# MCU.net
KiCad netlist of a schematic drawn in Altium Designer
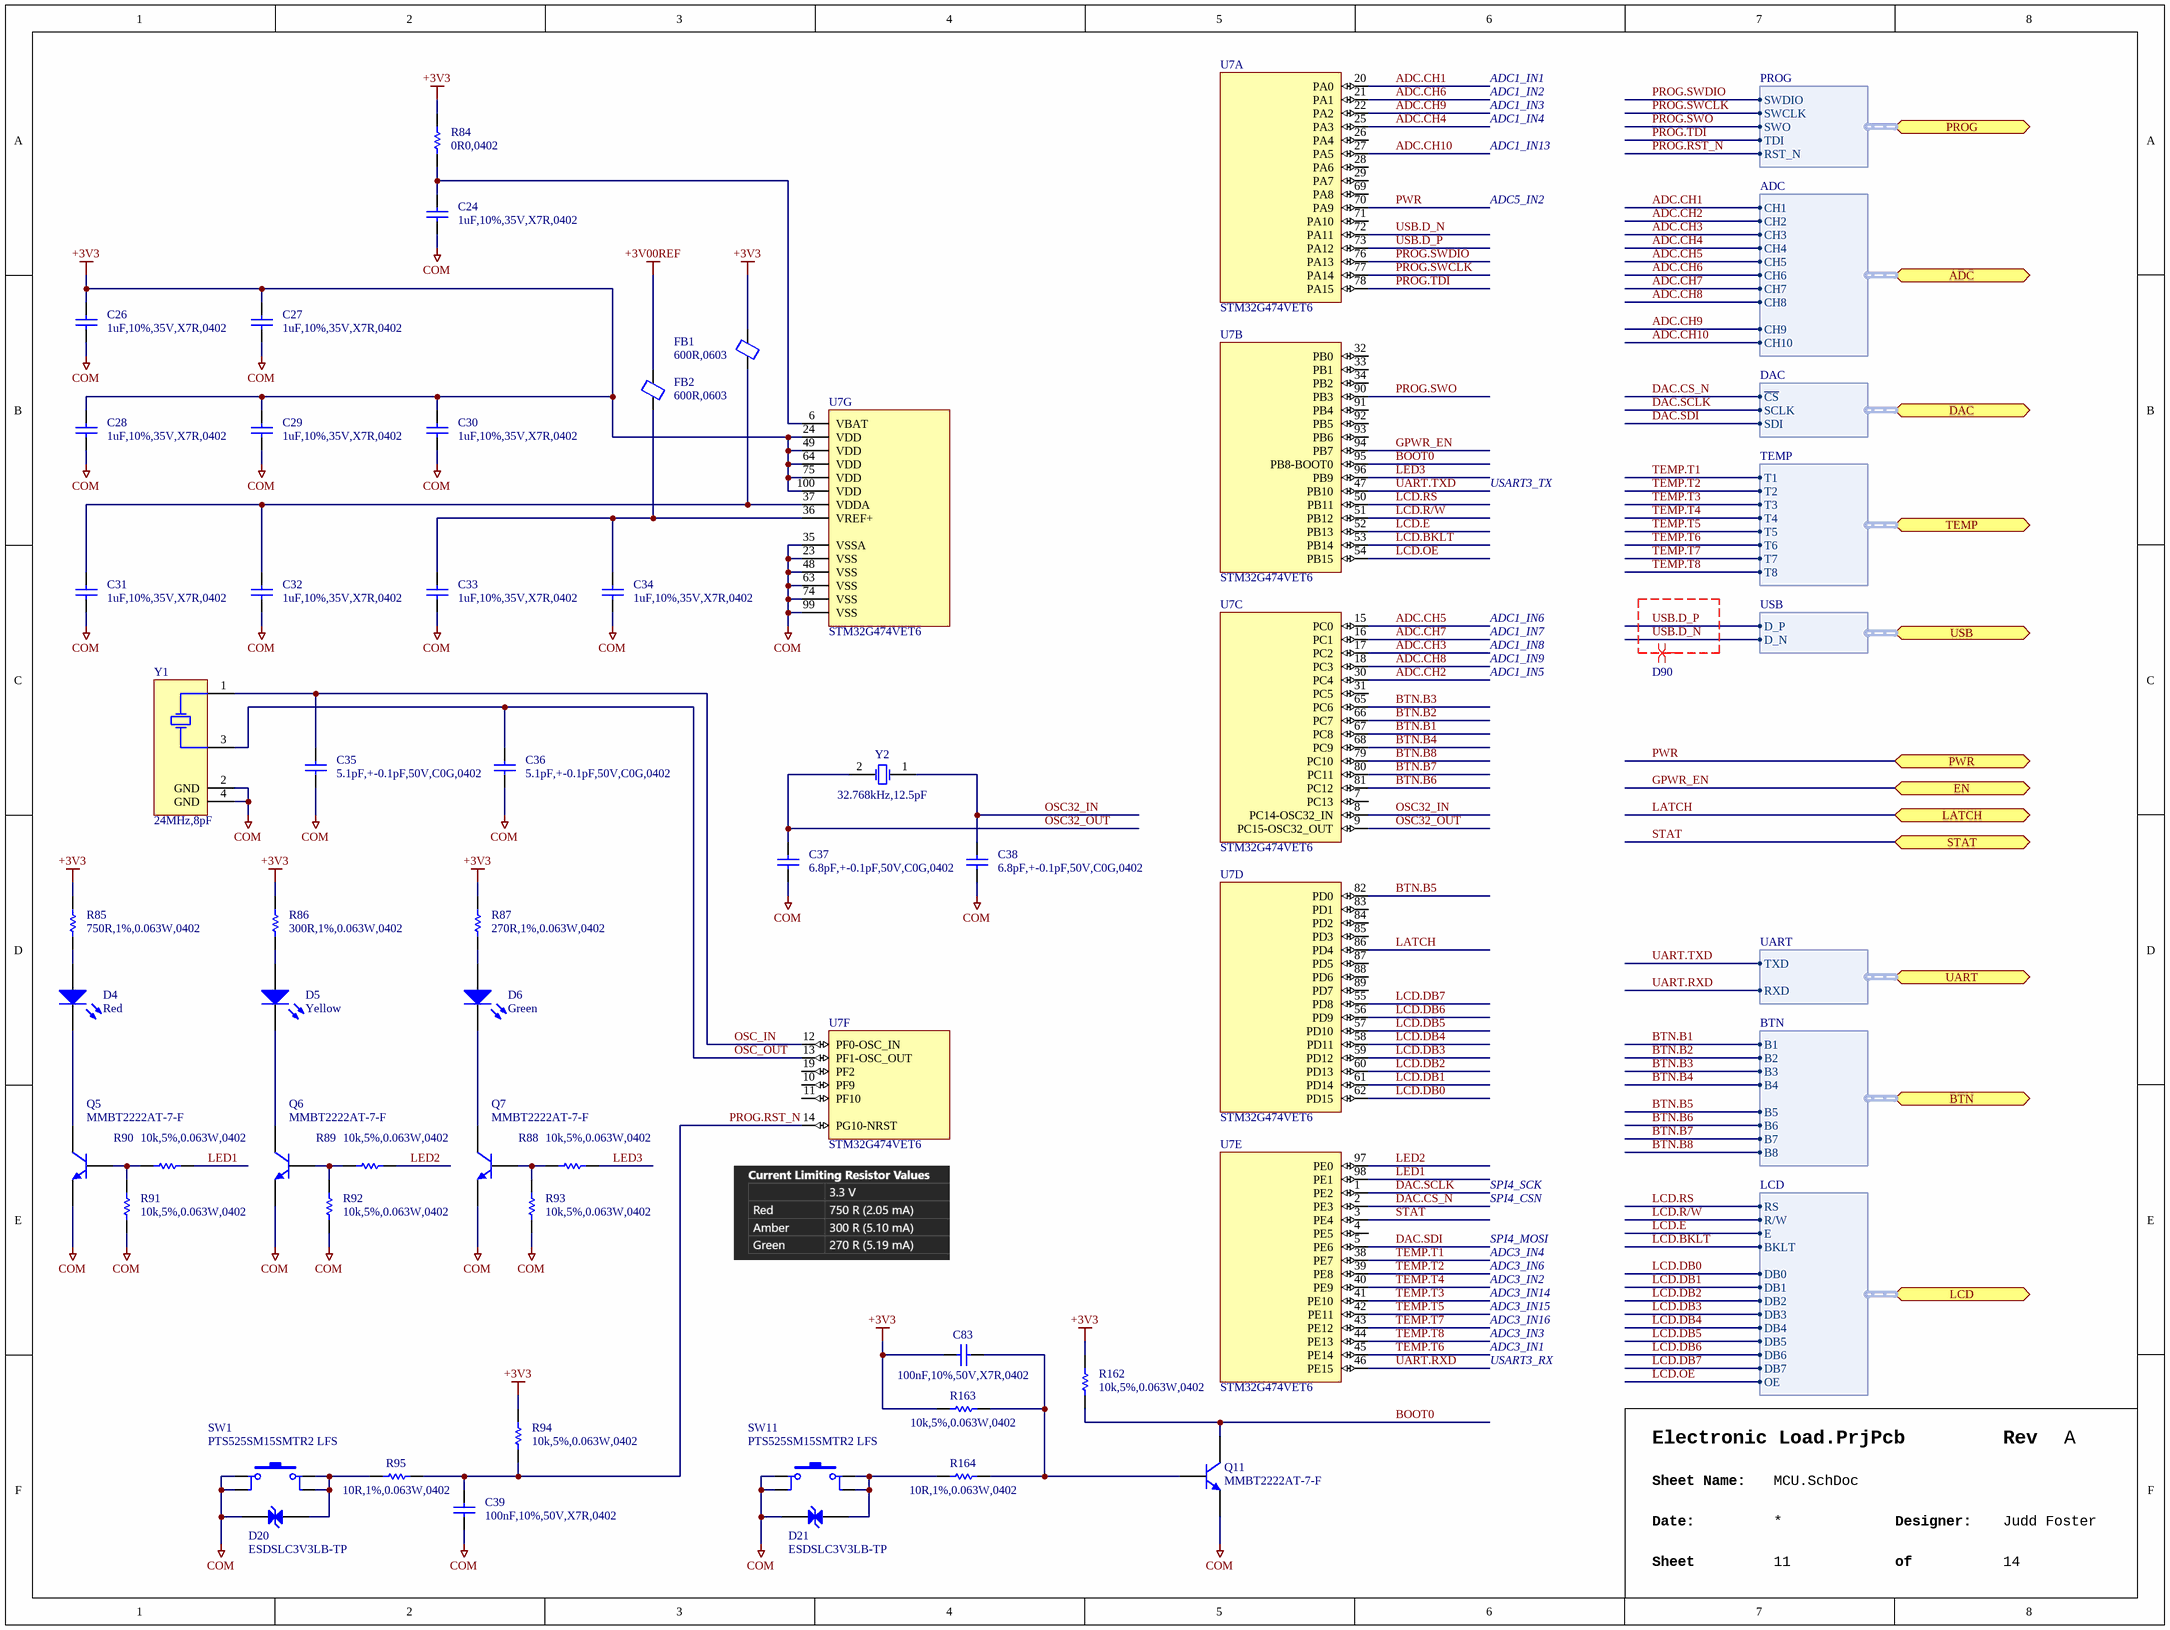
[diagram p0: MCU.SchDoc]

(export (version "E")
  (design (tool "Eeschema 10.0.6"))
  (components
    (comp (ref "C24")
      (value "1uF,10%,35V,X7R,0402")
      (footprint "CAPC1005X06N")
      (description "1 ï¿½F ï¿½10% 35V Ceramic Capacitor X5R 0402 (1005 Metric)")
      (fields
        (field (name "MANUFACTURER 1 PART NUMBER") "C1005X5R1V105K050BC")
        (field (name "VENDOR 1 PART NUMBER") "445-9073-1-ND")
        (field (name "CREATEDBY") "Judd Foster")
      )
      (libsource (lib "Component Library") (part "CAP,Cer,1uF,35VDC,X5R,0402"))
    )
    (comp (ref "C26")
      (value "1uF,10%,35V,X7R,0402")
      (footprint "CAPC1005X06N")
      (description "1 ï¿½F ï¿½10% 35V Ceramic Capacitor X5R 0402 (1005 Metric)")
      (fields
        (field (name "MANUFACTURER 1 PART NUMBER") "C1005X5R1V105K050BC")
        (field (name "VENDOR 1 PART NUMBER") "445-9073-1-ND")
        (field (name "CREATEDBY") "Judd Foster")
      )
      (libsource (lib "Component Library") (part "CAP,Cer,1uF,35VDC,X5R,0402"))
    )
    (comp (ref "C27")
      (value "1uF,10%,35V,X7R,0402")
      (footprint "CAPC1005X06N")
      (description "1 ï¿½F ï¿½10% 35V Ceramic Capacitor X5R 0402 (1005 Metric)")
      (fields
        (field (name "MANUFACTURER 1 PART NUMBER") "C1005X5R1V105K050BC")
        (field (name "VENDOR 1 PART NUMBER") "445-9073-1-ND")
        (field (name "CREATEDBY") "Judd Foster")
      )
      (libsource (lib "Component Library") (part "CAP,Cer,1uF,35VDC,X5R,0402"))
    )
    (comp (ref "C28")
      (value "1uF,10%,35V,X7R,0402")
      (footprint "CAPC1005X06N")
      (description "1 ï¿½F ï¿½10% 35V Ceramic Capacitor X5R 0402 (1005 Metric)")
      (fields
        (field (name "MANUFACTURER 1 PART NUMBER") "C1005X5R1V105K050BC")
        (field (name "VENDOR 1 PART NUMBER") "445-9073-1-ND")
        (field (name "CREATEDBY") "Judd Foster")
      )
      (libsource (lib "Component Library") (part "CAP,Cer,1uF,35VDC,X5R,0402"))
    )
    (comp (ref "C29")
      (value "1uF,10%,35V,X7R,0402")
      (footprint "CAPC1005X06N")
      (description "1 ï¿½F ï¿½10% 35V Ceramic Capacitor X5R 0402 (1005 Metric)")
      (fields
        (field (name "MANUFACTURER 1 PART NUMBER") "C1005X5R1V105K050BC")
        (field (name "VENDOR 1 PART NUMBER") "445-9073-1-ND")
        (field (name "CREATEDBY") "Judd Foster")
      )
      (libsource (lib "Component Library") (part "CAP,Cer,1uF,35VDC,X5R,0402"))
    )
    (comp (ref "C30")
      (value "1uF,10%,35V,X7R,0402")
      (footprint "CAPC1005X06N")
      (description "1 ï¿½F ï¿½10% 35V Ceramic Capacitor X5R 0402 (1005 Metric)")
      (fields
        (field (name "MANUFACTURER 1 PART NUMBER") "C1005X5R1V105K050BC")
        (field (name "VENDOR 1 PART NUMBER") "445-9073-1-ND")
        (field (name "CREATEDBY") "Judd Foster")
      )
      (libsource (lib "Component Library") (part "CAP,Cer,1uF,35VDC,X5R,0402"))
    )
    (comp (ref "C31")
      (value "1uF,10%,35V,X7R,0402")
      (footprint "CAPC1005X06N")
      (description "1 ï¿½F ï¿½10% 35V Ceramic Capacitor X5R 0402 (1005 Metric)")
      (fields
        (field (name "MANUFACTURER 1 PART NUMBER") "C1005X5R1V105K050BC")
        (field (name "VENDOR 1 PART NUMBER") "445-9073-1-ND")
        (field (name "CREATEDBY") "Judd Foster")
      )
      (libsource (lib "Component Library") (part "CAP,Cer,1uF,35VDC,X5R,0402"))
    )
    (comp (ref "C32")
      (value "1uF,10%,35V,X7R,0402")
      (footprint "CAPC1005X06N")
      (description "1 ï¿½F ï¿½10% 35V Ceramic Capacitor X5R 0402 (1005 Metric)")
      (fields
        (field (name "MANUFACTURER 1 PART NUMBER") "C1005X5R1V105K050BC")
        (field (name "VENDOR 1 PART NUMBER") "445-9073-1-ND")
        (field (name "CREATEDBY") "Judd Foster")
      )
      (libsource (lib "Component Library") (part "CAP,Cer,1uF,35VDC,X5R,0402"))
    )
    (comp (ref "C33")
      (value "1uF,10%,35V,X7R,0402")
      (footprint "CAPC1005X06N")
      (description "1 ï¿½F ï¿½10% 35V Ceramic Capacitor X5R 0402 (1005 Metric)")
      (fields
        (field (name "MANUFACTURER 1 PART NUMBER") "C1005X5R1V105K050BC")
        (field (name "VENDOR 1 PART NUMBER") "445-9073-1-ND")
        (field (name "CREATEDBY") "Judd Foster")
      )
      (libsource (lib "Component Library") (part "CAP,Cer,1uF,35VDC,X5R,0402"))
    )
    (comp (ref "C34")
      (value "1uF,10%,35V,X7R,0402")
      (footprint "CAPC1005X06N")
      (description "1 ï¿½F ï¿½10% 35V Ceramic Capacitor X5R 0402 (1005 Metric)")
      (fields
        (field (name "MANUFACTURER 1 PART NUMBER") "C1005X5R1V105K050BC")
        (field (name "VENDOR 1 PART NUMBER") "445-9073-1-ND")
        (field (name "CREATEDBY") "Judd Foster")
      )
      (libsource (lib "Component Library") (part "CAP,Cer,1uF,35VDC,X5R,0402"))
    )
    (comp (ref "C35")
      (value "5.1pF,+-0.1pF,50V,C0G,0402")
      (footprint "CAPC1005X06N")
      (description "50V 5.1pF C0G 0402 Ceramic Capacitors ROHS")
      (fields
        (field (name "MANUFACTURER 1 PART NUMBER") "GJM1555C1H5R1BB01D")
        (field (name "VENDOR 1 PART NUMBER") "C237535")
        (field (name "CREATEDBY") "Judd Foster")
      )
      (libsource (lib "Component Library") (part "CAP,NPOL"))
    )
    (comp (ref "C36")
      (value "5.1pF,+-0.1pF,50V,C0G,0402")
      (footprint "CAPC1005X06N")
      (description "50V 5.1pF C0G 0402 Ceramic Capacitors ROHS")
      (fields
        (field (name "MANUFACTURER 1 PART NUMBER") "GJM1555C1H5R1BB01D")
        (field (name "VENDOR 1 PART NUMBER") "C237535")
        (field (name "CREATEDBY") "Judd Foster")
      )
      (libsource (lib "Component Library") (part "CAP,NPOL"))
    )
    (comp (ref "C37")
      (value "6.8pF,+-0.1pF,50V,C0G,0402")
      (footprint "CAPC1005X06N")
      (description "50V 6.8pF C0G 0402 Ceramic Capacitors ROHS")
      (fields
        (field (name "MANUFACTURER 1 PART NUMBER") "GJM1555C1H6R8BB01D")
        (field (name "VENDOR 1 PART NUMBER") "C88896")
        (field (name "CREATEDBY") "Judd Foster")
      )
      (libsource (lib "Component Library") (part "CAP,NPOL"))
    )
    (comp (ref "C38")
      (value "6.8pF,+-0.1pF,50V,C0G,0402")
      (footprint "CAPC1005X06N")
      (description "50V 6.8pF C0G 0402 Ceramic Capacitors ROHS")
      (fields
        (field (name "MANUFACTURER 1 PART NUMBER") "GJM1555C1H6R8BB01D")
        (field (name "VENDOR 1 PART NUMBER") "C88896")
        (field (name "CREATEDBY") "Judd Foster")
      )
      (libsource (lib "Component Library") (part "CAP,NPOL"))
    )
    (comp (ref "C39")
      (value "100nF,10%,50V,X7R,0402")
      (footprint "CAPC1005X06N")
      (description "50V 100nF X7R Â±10% 0402 Ceramic Capacitors ROHS")
      (fields
        (field (name "MANUFACTURER 1 PART NUMBER") "GRM155R71H104KE14D")
        (field (name "VENDOR 1 PART NUMBER") "C77020")
        (field (name "CREATEDBY") "Judd Foster")
      )
      (libsource (lib "Component Library") (part "CAP,NPOL"))
    )
    (comp (ref "C83")
      (value "100nF,10%,50V,X7R,0402")
      (footprint "CAPC1005X06N")
      (description "50V 100nF X7R Â±10% 0402 Ceramic Capacitors ROHS")
      (fields
        (field (name "MANUFACTURER 1 PART NUMBER") "GRM155R71H104KE14D")
        (field (name "VENDOR 1 PART NUMBER") "C77020")
        (field (name "CREATEDBY") "Judd Foster")
      )
      (libsource (lib "Component Library") (part "CAP,NPOL"))
    )
    (comp (ref "D4")
      (value "Red")
      (footprint "LITE-ON_LTST-C190KRKT")
      (description "Red 631nm LED Indication - Discrete 2V 0603 (1608 Metric)")
      (fields
        (field (name "MANUFACTURER 1 PART NUMBER") "LTST-C190KRKT")
        (field (name "VENDOR 1 PART NUMBER") "160-1436-1-ND")
        (field (name "CREATEDBY") "Judd Foster")
      )
      (libsource (lib "Component Library") (part "LED,Red,SMD,0603"))
    )
    (comp (ref "D5")
      (value "Yellow")
      (footprint "LITE-ON_LTST-C190KSKT")
      (description "Yellow 591nm LED Indication - Discrete 2.1V 0603 (1608 Metric)")
      (fields
        (field (name "MANUFACTURER 1 PART NUMBER") "LTST-C190KSKT")
        (field (name "VENDOR 1 PART NUMBER") "160-1437-1-ND")
        (field (name "CREATEDBY") "Judd Foster")
      )
      (libsource (lib "Component Library") (part "LED,Yellow,SMD,0603"))
    )
    (comp (ref "D6")
      (value "Green")
      (footprint "LITE-ON_LTST-C190KGKT")
      (description "Green 571nm LED Indication - Discrete 2V 0603 (1608 Metric)")
      (fields
        (field (name "MANUFACTURER 1 PART NUMBER") "LTST-C190KGKT")
        (field (name "VENDOR 1 PART NUMBER") "160-1435-1-ND")
        (field (name "CREATEDBY") "Judd Foster")
      )
      (libsource (lib "Component Library") (part "LED,Green,SMD,0603"))
    )
    (comp (ref "D20")
      (value "ESDSLC3V3LB-TP")
      (footprint "DFN65P100X50-2N")
      (description "20V Clamp 5A (8/20ï¿½s) Ipp Tvs Diode Surface Mount DFN1006-2")
      (fields
        (field (name "VENDOR 1 PART NUMBER") "ESDSLC3V3LB-TPMSCT-ND")
        (field (name "CREATEDBY") "Judd Foster")
      )
      (libsource (lib "Component Library") (part "DIODE,TVS,3.3V,SOD882"))
    )
    (comp (ref "D21")
      (value "ESDSLC3V3LB-TP")
      (footprint "DFN65P100X50-2N")
      (description "20V Clamp 5A (8/20ï¿½s) Ipp Tvs Diode Surface Mount DFN1006-2")
      (fields
        (field (name "VENDOR 1 PART NUMBER") "ESDSLC3V3LB-TPMSCT-ND")
        (field (name "CREATEDBY") "Judd Foster")
      )
      (libsource (lib "Component Library") (part "DIODE,TVS,3.3V,SOD882"))
    )
    (comp (ref "FB1")
      (value "600R,0603")
      (footprint "INDC_0603")
      (description "500mÎ© Â±25% 600Î©@100MHz 0603 Ferrite Beads and Chips ROHS")
      (fields
        (field (name "MANUFACTURER 1 PART NUMBER") "FCM1608KF-601T03")
        (field (name "VENDOR 1 PART NUMBER") "C141723")
        (field (name "CREATEDBY") "Judd Foster")
      )
      (libsource (lib "Component Library") (part "FERRITE"))
    )
    (comp (ref "FB2")
      (value "600R,0603")
      (footprint "INDC_0603")
      (description "500mÎ© Â±25% 600Î©@100MHz 0603 Ferrite Beads and Chips ROHS")
      (fields
        (field (name "MANUFACTURER 1 PART NUMBER") "FCM1608KF-601T03")
        (field (name "VENDOR 1 PART NUMBER") "C141723")
        (field (name "CREATEDBY") "Judd Foster")
      )
      (libsource (lib "Component Library") (part "FERRITE"))
    )
    (comp (ref "Q5")
      (value "MMBT2222AT-7-F")
      (footprint "SOTFL50P160X90-3N")
      (description "Bipolar (BJT) Transistor NPN 40 V 600 mA 300MHz 150 mW Surface Mount SOT-523")
      (fields
        (field (name "VENDOR 1 PART NUMBER") "MMBT2222AT-FDICT-ND")
        (field (name "CREATEDBY") "Judd Foster")
      )
      (libsource (lib "Component Library") (part "Trans,NPN,40V,600mA,SOT523"))
    )
    (comp (ref "Q6")
      (value "MMBT2222AT-7-F")
      (footprint "SOTFL50P160X90-3N")
      (description "Bipolar (BJT) Transistor NPN 40 V 600 mA 300MHz 150 mW Surface Mount SOT-523")
      (fields
        (field (name "VENDOR 1 PART NUMBER") "MMBT2222AT-FDICT-ND")
        (field (name "CREATEDBY") "Judd Foster")
      )
      (libsource (lib "Component Library") (part "Trans,NPN,40V,600mA,SOT523"))
    )
    (comp (ref "Q7")
      (value "MMBT2222AT-7-F")
      (footprint "SOTFL50P160X90-3N")
      (description "Bipolar (BJT) Transistor NPN 40 V 600 mA 300MHz 150 mW Surface Mount SOT-523")
      (fields
        (field (name "VENDOR 1 PART NUMBER") "MMBT2222AT-FDICT-ND")
        (field (name "CREATEDBY") "Judd Foster")
      )
      (libsource (lib "Component Library") (part "Trans,NPN,40V,600mA,SOT523"))
    )
    (comp (ref "Q11")
      (value "MMBT2222AT-7-F")
      (footprint "SOTFL50P160X90-3N")
      (description "Bipolar (BJT) Transistor NPN 40 V 600 mA 300MHz 150 mW Surface Mount SOT-523")
      (fields
        (field (name "VENDOR 1 PART NUMBER") "MMBT2222AT-FDICT-ND")
        (field (name "CREATEDBY") "Judd Foster")
      )
      (libsource (lib "Component Library") (part "Trans,NPN,40V,600mA,SOT523"))
    )
    (comp (ref "R84")
      (value "0R0,0402")
      (footprint "RESC1005X04N")
      (description "0 Ohms Jumper 0.1W, 1/10W Chip Resistor 0402 (1005 Metric) Automotive AEC-Q200 Thick Film")
      (fields
        (field (name "MANUFACTURER 1 PART NUMBER") "ERJ-2GE0R00X")
        (field (name "VENDOR 1 PART NUMBER") "P0.0JCT-ND")
        (field (name "CREATEDBY") "Judd Foster")
      )
      (libsource (lib "Component Library") (part "RES,0R0,0402"))
    )
    (comp (ref "R85")
      (value "750R,1%,0.063W,0402")
      (footprint "RESC1005X04N")
      (description "750Î© 62.5mW 50V Â±100ppm/â„ƒ Thick Film Resistor Â±1% 0402 Chip Resistor - Surface Mount ROHS")
      (fields
        (field (name "MANUFACTURER 1 PART NUMBER") "0402WGF7500TCE")
        (field (name "VENDOR 1 PART NUMBER") "C25132")
        (field (name "CREATEDBY") "Judd Foster")
      )
      (libsource (lib "Component Library") (part "RES"))
    )
    (comp (ref "R86")
      (value "300R,1%,0.063W,0402")
      (footprint "RESC1005X04N")
      (description "300Î© 62.5mW 50V Â±100ppm/â„ƒ Thick Film Resistor Â±1% 0402 Chip Resistor - Surface Mount ROHS")
      (fields
        (field (name "MANUFACTURER 1 PART NUMBER") "0402WGF3000TCE")
        (field (name "VENDOR 1 PART NUMBER") "C25102")
        (field (name "CREATEDBY") "Judd Foster")
      )
      (libsource (lib "Component Library") (part "RES"))
    )
    (comp (ref "R87")
      (value "270R,1%,0.063W,0402")
      (footprint "RESC1005X04N")
      (description "62.5mW Thick Film Resistor 50V Â±100ppm/â„ƒ Â±1% 270Î© 0402 Chip Resistor - Surface Mount ROHS")
      (fields
        (field (name "MANUFACTURER 1 PART NUMBER") "RC0402FR-07270RL")
        (field (name "VENDOR 1 PART NUMBER") "C163474")
        (field (name "CREATEDBY") "Judd Foster")
      )
      (libsource (lib "Component Library") (part "RES"))
    )
    (comp (ref "R88")
      (value "10k,5%,0.063W,0402")
      (footprint "RESC1005X04N")
      (description "10 kOhms ï¿½5% 0.063W, 1/16W Chip Resistor 0402 (1005 Metric) Automotive AEC-Q200 Thick Film")
      (fields
        (field (name "MANUFACTURER 1 PART NUMBER") "RMCF0402JT10K0")
        (field (name "VENDOR 1 PART NUMBER") "RMCF0402JT10K0CT-ND")
        (field (name "CREATEDBY") "Judd Foster")
      )
      (libsource (lib "Component Library") (part "RES,10k,5%,0.063W,0402"))
    )
    (comp (ref "R89")
      (value "10k,5%,0.063W,0402")
      (footprint "RESC1005X04N")
      (description "10 kOhms ï¿½5% 0.063W, 1/16W Chip Resistor 0402 (1005 Metric) Automotive AEC-Q200 Thick Film")
      (fields
        (field (name "MANUFACTURER 1 PART NUMBER") "RMCF0402JT10K0")
        (field (name "VENDOR 1 PART NUMBER") "RMCF0402JT10K0CT-ND")
        (field (name "CREATEDBY") "Judd Foster")
      )
      (libsource (lib "Component Library") (part "RES,10k,5%,0.063W,0402"))
    )
    (comp (ref "R90")
      (value "10k,5%,0.063W,0402")
      (footprint "RESC1005X04N")
      (description "10 kOhms ï¿½5% 0.063W, 1/16W Chip Resistor 0402 (1005 Metric) Automotive AEC-Q200 Thick Film")
      (fields
        (field (name "MANUFACTURER 1 PART NUMBER") "RMCF0402JT10K0")
        (field (name "VENDOR 1 PART NUMBER") "RMCF0402JT10K0CT-ND")
        (field (name "CREATEDBY") "Judd Foster")
      )
      (libsource (lib "Component Library") (part "RES,10k,5%,0.063W,0402"))
    )
    (comp (ref "R91")
      (value "10k,5%,0.063W,0402")
      (footprint "RESC1005X04N")
      (description "10 kOhms ï¿½5% 0.063W, 1/16W Chip Resistor 0402 (1005 Metric) Automotive AEC-Q200 Thick Film")
      (fields
        (field (name "MANUFACTURER 1 PART NUMBER") "RMCF0402JT10K0")
        (field (name "VENDOR 1 PART NUMBER") "RMCF0402JT10K0CT-ND")
        (field (name "CREATEDBY") "Judd Foster")
      )
      (libsource (lib "Component Library") (part "RES,10k,5%,0.063W,0402"))
    )
    (comp (ref "R92")
      (value "10k,5%,0.063W,0402")
      (footprint "RESC1005X04N")
      (description "10 kOhms ï¿½5% 0.063W, 1/16W Chip Resistor 0402 (1005 Metric) Automotive AEC-Q200 Thick Film")
      (fields
        (field (name "MANUFACTURER 1 PART NUMBER") "RMCF0402JT10K0")
        (field (name "VENDOR 1 PART NUMBER") "RMCF0402JT10K0CT-ND")
        (field (name "CREATEDBY") "Judd Foster")
      )
      (libsource (lib "Component Library") (part "RES,10k,5%,0.063W,0402"))
    )
    (comp (ref "R93")
      (value "10k,5%,0.063W,0402")
      (footprint "RESC1005X04N")
      (description "10 kOhms ï¿½5% 0.063W, 1/16W Chip Resistor 0402 (1005 Metric) Automotive AEC-Q200 Thick Film")
      (fields
        (field (name "MANUFACTURER 1 PART NUMBER") "RMCF0402JT10K0")
        (field (name "VENDOR 1 PART NUMBER") "RMCF0402JT10K0CT-ND")
        (field (name "CREATEDBY") "Judd Foster")
      )
      (libsource (lib "Component Library") (part "RES,10k,5%,0.063W,0402"))
    )
    (comp (ref "R94")
      (value "10k,5%,0.063W,0402")
      (footprint "RESC1005X04N")
      (description "10 kOhms ï¿½5% 0.063W, 1/16W Chip Resistor 0402 (1005 Metric) Automotive AEC-Q200 Thick Film")
      (fields
        (field (name "MANUFACTURER 1 PART NUMBER") "RMCF0402JT10K0")
        (field (name "VENDOR 1 PART NUMBER") "RMCF0402JT10K0CT-ND")
        (field (name "CREATEDBY") "Judd Foster")
      )
      (libsource (lib "Component Library") (part "RES,10k,5%,0.063W,0402"))
    )
    (comp (ref "R95")
      (value "10R,1%,0.063W,0402")
      (footprint "RESC1005X04N")
      (description "10 Ohms ï¿½1% 0.063W, 1/16W Chip Resistor 0402 (1005 Metric) Automotive AEC-Q200 Thick Film")
      (fields
        (field (name "MANUFACTURER 1 PART NUMBER") "ERJ-2RKF10R0X")
        (field (name "VENDOR 1 PART NUMBER") "P10.0LCT-ND")
        (field (name "CREATEDBY") "Judd Foster")
      )
      (libsource (lib "Component Library") (part "RES,10R,1%,0.063W,0402"))
    )
    (comp (ref "R162")
      (value "10k,5%,0.063W,0402")
      (footprint "RESC1005X04N")
      (description "10 kOhms ï¿½5% 0.063W, 1/16W Chip Resistor 0402 (1005 Metric) Automotive AEC-Q200 Thick Film")
      (fields
        (field (name "MANUFACTURER 1 PART NUMBER") "RMCF0402JT10K0")
        (field (name "VENDOR 1 PART NUMBER") "RMCF0402JT10K0CT-ND")
        (field (name "CREATEDBY") "Judd Foster")
      )
      (libsource (lib "Component Library") (part "RES,10k,5%,0.063W,0402"))
    )
    (comp (ref "R163")
      (value "10k,5%,0.063W,0402")
      (footprint "RESC1005X04N")
      (description "10 kOhms ï¿½5% 0.063W, 1/16W Chip Resistor 0402 (1005 Metric) Automotive AEC-Q200 Thick Film")
      (fields
        (field (name "MANUFACTURER 1 PART NUMBER") "RMCF0402JT10K0")
        (field (name "VENDOR 1 PART NUMBER") "RMCF0402JT10K0CT-ND")
        (field (name "CREATEDBY") "Judd Foster")
      )
      (libsource (lib "Component Library") (part "RES,10k,5%,0.063W,0402"))
    )
    (comp (ref "R164")
      (value "10R,1%,0.063W,0402")
      (footprint "RESC1005X04N")
      (description "10 Ohms ï¿½1% 0.063W, 1/16W Chip Resistor 0402 (1005 Metric) Automotive AEC-Q200 Thick Film")
      (fields
        (field (name "MANUFACTURER 1 PART NUMBER") "ERJ-2RKF10R0X")
        (field (name "VENDOR 1 PART NUMBER") "P10.0LCT-ND")
        (field (name "CREATEDBY") "Judd Foster")
      )
      (libsource (lib "Component Library") (part "RES,10R,1%,0.063W,0402"))
    )
    (comp (ref "SW1")
      (value "PTS525SM15SMTR2 LFS")
      (footprint "C&K_PTS525SM15SMTR2 LFS")
      (description "Tactile Switch SPST-NO Top Actuated Surface Mount")
      (fields (field (name "VENDOR 1 PART NUMBER") "CKN9104CT-ND") (field (name "CREATEDBY") "Judd Foster"))
      (libsource (lib "Component Library") (part "Switch,Tactile,SPST-NO,SMD,H1.5"))
    )
    (comp (ref "SW11")
      (value "PTS525SM15SMTR2 LFS")
      (footprint "C&K_PTS525SM15SMTR2 LFS")
      (description "Tactile Switch SPST-NO Top Actuated Surface Mount")
      (fields (field (name "VENDOR 1 PART NUMBER") "CKN9104CT-ND") (field (name "CREATEDBY") "Judd Foster"))
      (libsource (lib "Component Library") (part "Switch,Tactile,SPST-NO,SMD,H1.5"))
    )
    (comp (ref "U7")
      (value "STM32G474VET6")
      (footprint "STMICROELECTRONICS_PKG_LQFP100")
      (description "ARM Cortex-M Series 170MHz 86 LQFP-100(14x14) Microcontrollers ROHS")
      (fields (field (name "VENDOR 1 PART NUMBER") "C431632") (field (name "CREATEDBY") "Judd Foster"))
      (libsource (lib "Component Library") (part "STM32G474VET6"))
    )
    (comp (ref "Y1")
      (value "24MHz,8pF")
      (footprint "NDK_NX2016SA")
      (description "SMD2016-4P Crystals ROHS")
      (fields
        (field (name "MANUFACTURER 1 PART NUMBER") "NX2016SA-24MHZ-STD-CZS-2")
        (field (name "VENDOR 1 PART NUMBER") "C843257")
        (field (name "CREATEDBY") "Judd Foster")
      )
      (libsource (lib "Component Library") (part "XTAL,24MHz,8pF,SMD"))
    )
    (comp (ref "Y2")
      (value "32.768kHz,12.5pF")
      (footprint "EPSON_FC-135")
      (description "Crystal Oscillator 12.5pF SMD3215-2P Crystals ROHS")
      (fields
        (field (name "MANUFACTURER 1 PART NUMBER") "Q13FC13500004")
        (field (name "VENDOR 1 PART NUMBER") "C32346")
        (field (name "CREATEDBY") "Judd Foster")
      )
      (libsource (lib "Component Library") (part "XTAL,32.768kHz,12.5pF,SMD"))
    )
  )
  (nets
    (net (code "9") (name "+3V00REF") (class "Default")
      (node (ref "FB2") (pin "2") (pinfunction "2_2") (pintype "passive"))
    )
    (net (code "10") (name "+3V3") (class "Default")
      (node (ref "C26") (pin "2") (pinfunction "2_2") (pintype "passive"))
      (node (ref "C27") (pin "2") (pinfunction "2_2") (pintype "passive"))
      (node (ref "C28") (pin "2") (pinfunction "2_2") (pintype "passive"))
      (node (ref "C29") (pin "2") (pinfunction "2_2") (pintype "passive"))
      (node (ref "C30") (pin "2") (pinfunction "2_2") (pintype "passive"))
      (node (ref "C83") (pin "2") (pinfunction "2_2") (pintype "passive"))
      (node (ref "FB1") (pin "2") (pinfunction "2_2") (pintype "passive"))
      (node (ref "R162") (pin "1") (pinfunction "1_1") (pintype "passive"))
      (node (ref "R163") (pin "2") (pinfunction "2_2") (pintype "passive"))
      (node (ref "R84") (pin "2") (pinfunction "2_2") (pintype "passive"))
      (node (ref "R85") (pin "2") (pinfunction "2_2") (pintype "passive"))
      (node (ref "R86") (pin "2") (pinfunction "2_2") (pintype "passive"))
      (node (ref "R87") (pin "2") (pinfunction "2_2") (pintype "passive"))
      (node (ref "R94") (pin "2") (pinfunction "2_2") (pintype "passive"))
      (node (ref "U7") (pin "100") (pinfunction "VDD_100") (pintype "power_in"))
      (node (ref "U7") (pin "24") (pinfunction "VDD_24") (pintype "power_in"))
      (node (ref "U7") (pin "49") (pinfunction "VDD_49") (pintype "power_in"))
      (node (ref "U7") (pin "64") (pinfunction "VDD_64") (pintype "power_in"))
      (node (ref "U7") (pin "75") (pinfunction "VDD_75") (pintype "power_in"))
    )
    (net (code "11") (name "/ADC.CH1") (class "Default")
      (node (ref "U7") (pin "20") (pinfunction "PA0_20") (pintype "bidirectional"))
    )
    (net (code "12") (name "/ADC.CH2") (class "Default")
      (node (ref "U7") (pin "30") (pinfunction "PC4_30") (pintype "bidirectional"))
    )
    (net (code "13") (name "/ADC.CH3") (class "Default")
      (node (ref "U7") (pin "17") (pinfunction "PC2_17") (pintype "bidirectional"))
    )
    (net (code "14") (name "/ADC.CH4") (class "Default")
      (node (ref "U7") (pin "25") (pinfunction "PA3_25") (pintype "bidirectional"))
    )
    (net (code "15") (name "/ADC.CH5") (class "Default")
      (node (ref "U7") (pin "15") (pinfunction "PC0_15") (pintype "bidirectional"))
    )
    (net (code "16") (name "/ADC.CH6") (class "Default")
      (node (ref "U7") (pin "21") (pinfunction "PA1_21") (pintype "bidirectional"))
    )
    (net (code "17") (name "/ADC.CH7") (class "Default")
      (node (ref "U7") (pin "16") (pinfunction "PC1_16") (pintype "bidirectional"))
    )
    (net (code "18") (name "/ADC.CH8") (class "Default")
      (node (ref "U7") (pin "18") (pinfunction "PC3_18") (pintype "bidirectional"))
    )
    (net (code "19") (name "/ADC.CH9") (class "Default")
      (node (ref "U7") (pin "22") (pinfunction "PA2_22") (pintype "bidirectional"))
    )
    (net (code "20") (name "/ADC.CH10") (class "Default")
      (node (ref "U7") (pin "27") (pinfunction "PA5_27") (pintype "bidirectional"))
    )
    (net (code "21") (name "/BOOT0") (class "Default")
      (node (ref "Q11") (pin "3") (pinfunction "C_3") (pintype "passive"))
      (node (ref "R162") (pin "2") (pinfunction "2_2") (pintype "passive"))
      (node (ref "U7") (pin "95") (pinfunction "PB8-BOOT0_95") (pintype "bidirectional"))
    )
    (net (code "22") (name "/BTN.B1") (class "Default")
      (node (ref "U7") (pin "67") (pinfunction "PC8_67") (pintype "bidirectional"))
    )
    (net (code "23") (name "/BTN.B2") (class "Default")
      (node (ref "U7") (pin "66") (pinfunction "PC7_66") (pintype "bidirectional"))
    )
    (net (code "24") (name "/BTN.B3") (class "Default")
      (node (ref "U7") (pin "65") (pinfunction "PC6_65") (pintype "bidirectional"))
    )
    (net (code "25") (name "/BTN.B4") (class "Default")
      (node (ref "U7") (pin "68") (pinfunction "PC9_68") (pintype "bidirectional"))
    )
    (net (code "26") (name "/BTN.B5") (class "Default")
      (node (ref "U7") (pin "82") (pinfunction "PD0_82") (pintype "bidirectional"))
    )
    (net (code "27") (name "/BTN.B6") (class "Default")
      (node (ref "U7") (pin "81") (pinfunction "PC12_81") (pintype "bidirectional"))
    )
    (net (code "28") (name "/BTN.B7") (class "Default")
      (node (ref "U7") (pin "80") (pinfunction "PC11_80") (pintype "bidirectional"))
    )
    (net (code "29") (name "/BTN.B8") (class "Default")
      (node (ref "U7") (pin "79") (pinfunction "PC10_79") (pintype "bidirectional"))
    )
    (net (code "30") (name "/DAC.CS_N") (class "Default")
      (node (ref "U7") (pin "2") (pinfunction "PE3_2") (pintype "bidirectional"))
    )
    (net (code "31") (name "/DAC.SCLK") (class "Default")
      (node (ref "U7") (pin "1") (pinfunction "PE2_1") (pintype "bidirectional"))
    )
    (net (code "32") (name "/DAC.SDI") (class "Default")
      (node (ref "U7") (pin "5") (pinfunction "PE6_5") (pintype "bidirectional"))
    )
    (net (code "33") (name "/GPWR_EN") (class "Default")
      (node (ref "U7") (pin "94") (pinfunction "PB7_94") (pintype "bidirectional"))
    )
    (net (code "34") (name "/LATCH") (class "Default")
      (node (ref "U7") (pin "86") (pinfunction "PD4_86") (pintype "bidirectional"))
    )
    (net (code "35") (name "/LCD.BKLT") (class "Default")
      (node (ref "U7") (pin "53") (pinfunction "PB14_53") (pintype "bidirectional"))
    )
    (net (code "36") (name "/LCD.DB0") (class "Default")
      (node (ref "U7") (pin "62") (pinfunction "PD15_62") (pintype "bidirectional"))
    )
    (net (code "37") (name "/LCD.DB1") (class "Default")
      (node (ref "U7") (pin "61") (pinfunction "PD14_61") (pintype "bidirectional"))
    )
    (net (code "38") (name "/LCD.DB2") (class "Default")
      (node (ref "U7") (pin "60") (pinfunction "PD13_60") (pintype "bidirectional"))
    )
    (net (code "39") (name "/LCD.DB3") (class "Default")
      (node (ref "U7") (pin "59") (pinfunction "PD12_59") (pintype "bidirectional"))
    )
    (net (code "40") (name "/LCD.DB4") (class "Default")
      (node (ref "U7") (pin "58") (pinfunction "PD11_58") (pintype "bidirectional"))
    )
    (net (code "41") (name "/LCD.DB5") (class "Default")
      (node (ref "U7") (pin "57") (pinfunction "PD10_57") (pintype "bidirectional"))
    )
    (net (code "42") (name "/LCD.DB6") (class "Default")
      (node (ref "U7") (pin "56") (pinfunction "PD9_56") (pintype "bidirectional"))
    )
    (net (code "43") (name "/LCD.DB7") (class "Default")
      (node (ref "U7") (pin "55") (pinfunction "PD8_55") (pintype "bidirectional"))
    )
    (net (code "44") (name "/LCD.E") (class "Default")
      (node (ref "U7") (pin "52") (pinfunction "PB13_52") (pintype "bidirectional"))
    )
    (net (code "45") (name "/LCD.OE") (class "Default")
      (node (ref "U7") (pin "54") (pinfunction "PB15_54") (pintype "bidirectional"))
    )
    (net (code "46") (name "/LCD.RS") (class "Default")
      (node (ref "U7") (pin "50") (pinfunction "PB11_50") (pintype "bidirectional"))
    )
    (net (code "47") (name "/LCD.R{slash}W") (class "Default")
      (node (ref "U7") (pin "51") (pinfunction "PB12_51") (pintype "bidirectional"))
    )
    (net (code "48") (name "/LED1") (class "Default")
      (node (ref "R90") (pin "1") (pinfunction "1_1") (pintype "passive"))
      (node (ref "U7") (pin "98") (pinfunction "PE1_98") (pintype "bidirectional"))
    )
    (net (code "49") (name "/LED2") (class "Default")
      (node (ref "R89") (pin "1") (pinfunction "1_1") (pintype "passive"))
      (node (ref "U7") (pin "97") (pinfunction "PE0_97") (pintype "bidirectional"))
    )
    (net (code "50") (name "/LED3") (class "Default")
      (node (ref "R88") (pin "1") (pinfunction "1_1") (pintype "passive"))
      (node (ref "U7") (pin "96") (pinfunction "PB9_96") (pintype "bidirectional"))
    )
    (net (code "51") (name "/OSC32_IN") (class "Default")
      (node (ref "C38") (pin "2") (pinfunction "2_2") (pintype "passive"))
      (node (ref "U7") (pin "8") (pinfunction "PC14-OSC32_IN_8") (pintype "bidirectional"))
      (node (ref "Y2") (pin "1") (pinfunction "OSC1_1") (pintype "passive"))
    )
    (net (code "52") (name "/OSC32_OUT") (class "Default")
      (node (ref "C37") (pin "2") (pinfunction "2_2") (pintype "passive"))
      (node (ref "U7") (pin "9") (pinfunction "PC15-OSC32_OUT_9") (pintype "bidirectional"))
      (node (ref "Y2") (pin "2") (pinfunction "GND_2") (pintype "passive"))
    )
    (net (code "53") (name "/OSC_IN") (class "Default")
      (node (ref "C35") (pin "2") (pinfunction "2_2") (pintype "passive"))
      (node (ref "U7") (pin "12") (pinfunction "PF0-OSC_IN_12") (pintype "bidirectional"))
      (node (ref "Y1") (pin "1") (pinfunction "OSC1_1") (pintype "passive"))
    )
    (net (code "54") (name "/OSC_OUT") (class "Default")
      (node (ref "C36") (pin "2") (pinfunction "2_2") (pintype "passive"))
      (node (ref "U7") (pin "13") (pinfunction "PF1-OSC_OUT_13") (pintype "bidirectional"))
      (node (ref "Y1") (pin "3") (pinfunction "OSC2_3") (pintype "passive"))
    )
    (net (code "55") (name "/PROG.RST_N") (class "Default")
      (node (ref "C39") (pin "2") (pinfunction "2_2") (pintype "passive"))
      (node (ref "R94") (pin "1") (pinfunction "1_1") (pintype "passive"))
      (node (ref "R95") (pin "2") (pinfunction "2_2") (pintype "passive"))
      (node (ref "U7") (pin "14") (pinfunction "PG10-NRST_14") (pintype "bidirectional"))
    )
    (net (code "56") (name "/PROG.SWCLK") (class "Default")
      (node (ref "U7") (pin "77") (pinfunction "PA14_77") (pintype "bidirectional"))
    )
    (net (code "57") (name "/PROG.SWDIO") (class "Default")
      (node (ref "U7") (pin "76") (pinfunction "PA13_76") (pintype "bidirectional"))
    )
    (net (code "58") (name "/PROG.SWO") (class "Default")
      (node (ref "U7") (pin "90") (pinfunction "PB3_90") (pintype "bidirectional"))
    )
    (net (code "59") (name "/PROG.TDI") (class "Default")
      (node (ref "U7") (pin "78") (pinfunction "PA15_78") (pintype "bidirectional"))
    )
    (net (code "60") (name "/PWR") (class "Default")
      (node (ref "U7") (pin "70") (pinfunction "PA9_70") (pintype "bidirectional"))
    )
    (net (code "61") (name "/STAT") (class "Default")
      (node (ref "U7") (pin "3") (pinfunction "PE4_3") (pintype "bidirectional"))
    )
    (net (code "62") (name "/TEMP.T1") (class "Default")
      (node (ref "U7") (pin "38") (pinfunction "PE7_38") (pintype "bidirectional"))
    )
    (net (code "63") (name "/TEMP.T2") (class "Default")
      (node (ref "U7") (pin "39") (pinfunction "PE8_39") (pintype "bidirectional"))
    )
    (net (code "64") (name "/TEMP.T3") (class "Default")
      (node (ref "U7") (pin "41") (pinfunction "PE10_41") (pintype "bidirectional"))
    )
    (net (code "65") (name "/TEMP.T4") (class "Default")
      (node (ref "U7") (pin "40") (pinfunction "PE9_40") (pintype "bidirectional"))
    )
    (net (code "66") (name "/TEMP.T5") (class "Default")
      (node (ref "U7") (pin "42") (pinfunction "PE11_42") (pintype "bidirectional"))
    )
    (net (code "67") (name "/TEMP.T6") (class "Default")
      (node (ref "U7") (pin "45") (pinfunction "PE14_45") (pintype "bidirectional"))
    )
    (net (code "68") (name "/TEMP.T7") (class "Default")
      (node (ref "U7") (pin "43") (pinfunction "PE12_43") (pintype "bidirectional"))
    )
    (net (code "69") (name "/TEMP.T8") (class "Default")
      (node (ref "U7") (pin "44") (pinfunction "PE13_44") (pintype "bidirectional"))
    )
    (net (code "70") (name "/UART.RXD") (class "Default")
      (node (ref "U7") (pin "46") (pinfunction "PE15_46") (pintype "bidirectional"))
    )
    (net (code "71") (name "/UART.TXD") (class "Default")
      (node (ref "U7") (pin "47") (pinfunction "PB10_47") (pintype "bidirectional"))
    )
    (net (code "72") (name "/USB.D_N") (class "Default")
      (node (ref "U7") (pin "72") (pinfunction "PA11_72") (pintype "bidirectional"))
    )
    (net (code "73") (name "/USB.D_P") (class "Default")
      (node (ref "U7") (pin "73") (pinfunction "PA12_73") (pintype "bidirectional"))
    )
    (net (code "82") (name "COM") (class "Default")
      (node (ref "C24") (pin "1") (pinfunction "1_1") (pintype "passive"))
      (node (ref "C26") (pin "1") (pinfunction "1_1") (pintype "passive"))
      (node (ref "C27") (pin "1") (pinfunction "1_1") (pintype "passive"))
      (node (ref "C28") (pin "1") (pinfunction "1_1") (pintype "passive"))
      (node (ref "C29") (pin "1") (pinfunction "1_1") (pintype "passive"))
      (node (ref "C30") (pin "1") (pinfunction "1_1") (pintype "passive"))
      (node (ref "C31") (pin "1") (pinfunction "1_1") (pintype "passive"))
      (node (ref "C32") (pin "1") (pinfunction "1_1") (pintype "passive"))
      (node (ref "C33") (pin "1") (pinfunction "1_1") (pintype "passive"))
      (node (ref "C34") (pin "1") (pinfunction "1_1") (pintype "passive"))
      (node (ref "C35") (pin "1") (pinfunction "1_1") (pintype "passive"))
      (node (ref "C36") (pin "1") (pinfunction "1_1") (pintype "passive"))
      (node (ref "C37") (pin "1") (pinfunction "1_1") (pintype "passive"))
      (node (ref "C38") (pin "1") (pinfunction "1_1") (pintype "passive"))
      (node (ref "C39") (pin "1") (pinfunction "1_1") (pintype "passive"))
      (node (ref "D20") (pin "1") (pinfunction "K_1") (pintype "passive"))
      (node (ref "D21") (pin "1") (pinfunction "K_1") (pintype "passive"))
      (node (ref "Q11") (pin "2") (pinfunction "E_2") (pintype "passive"))
      (node (ref "Q5") (pin "2") (pinfunction "E_2") (pintype "passive"))
      (node (ref "Q6") (pin "2") (pinfunction "E_2") (pintype "passive"))
      (node (ref "Q7") (pin "2") (pinfunction "E_2") (pintype "passive"))
      (node (ref "R91") (pin "1") (pinfunction "1_1") (pintype "passive"))
      (node (ref "R92") (pin "1") (pinfunction "1_1") (pintype "passive"))
      (node (ref "R93") (pin "1") (pinfunction "1_1") (pintype "passive"))
      (node (ref "SW1") (pin "1") (pinfunction "1_1") (pintype "passive"))
      (node (ref "SW1") (pin "2") (pinfunction "2_2") (pintype "passive"))
      (node (ref "SW11") (pin "1") (pinfunction "1_1") (pintype "passive"))
      (node (ref "SW11") (pin "2") (pinfunction "2_2") (pintype "passive"))
      (node (ref "U7") (pin "23") (pinfunction "VSS_23") (pintype "power_in"))
      (node (ref "U7") (pin "35") (pinfunction "VSSA_35") (pintype "power_in"))
      (node (ref "U7") (pin "48") (pinfunction "VSS_48") (pintype "power_in"))
      (node (ref "U7") (pin "63") (pinfunction "VSS_63") (pintype "power_in"))
      (node (ref "U7") (pin "74") (pinfunction "VSS_74") (pintype "power_in"))
      (node (ref "U7") (pin "99") (pinfunction "VSS_99") (pintype "power_in"))
      (node (ref "Y1") (pin "2") (pinfunction "GND_2") (pintype "passive"))
      (node (ref "Y1") (pin "4") (pinfunction "GND_4") (pintype "passive"))
    )
    (net (code "83") (name "Net-(D4-PadA)") (class "Default")
      (node (ref "D4") (pin "A") (pinfunction "A_A") (pintype "passive"))
      (node (ref "R85") (pin "1") (pinfunction "1_1") (pintype "passive"))
    )
    (net (code "84") (name "Net-(D5-PadA)") (class "Default")
      (node (ref "D5") (pin "A") (pinfunction "A_A") (pintype "passive"))
      (node (ref "R86") (pin "1") (pinfunction "1_1") (pintype "passive"))
    )
    (net (code "85") (name "Net-(D6-PadA)") (class "Default")
      (node (ref "D6") (pin "A") (pinfunction "A_A") (pintype "passive"))
      (node (ref "R87") (pin "1") (pinfunction "1_1") (pintype "passive"))
    )
    (net (code "86") (name "Net-(D20-A)") (class "Default")
      (node (ref "D20") (pin "2") (pinfunction "A_2") (pintype "passive"))
      (node (ref "R95") (pin "1") (pinfunction "1_1") (pintype "passive"))
      (node (ref "SW1") (pin "3") (pinfunction "3_3") (pintype "passive"))
      (node (ref "SW1") (pin "4") (pinfunction "4_4") (pintype "passive"))
    )
    (net (code "87") (name "Net-(D21-A)") (class "Default")
      (node (ref "D21") (pin "2") (pinfunction "A_2") (pintype "passive"))
      (node (ref "R164") (pin "1") (pinfunction "1_1") (pintype "passive"))
      (node (ref "SW11") (pin "3") (pinfunction "3_3") (pintype "passive"))
      (node (ref "SW11") (pin "4") (pinfunction "4_4") (pintype "passive"))
    )
    (net (code "88") (name "Net-(Q5-B)") (class "Default")
      (node (ref "Q5") (pin "1") (pinfunction "B_1") (pintype "passive"))
      (node (ref "R90") (pin "2") (pinfunction "2_2") (pintype "passive"))
      (node (ref "R91") (pin "2") (pinfunction "2_2") (pintype "passive"))
    )
    (net (code "89") (name "Net-(Q5-C)") (class "Default")
      (node (ref "D4") (pin "C") (pinfunction "C_C") (pintype "passive"))
      (node (ref "Q5") (pin "3") (pinfunction "C_3") (pintype "passive"))
    )
    (net (code "90") (name "Net-(Q6-B)") (class "Default")
      (node (ref "Q6") (pin "1") (pinfunction "B_1") (pintype "passive"))
      (node (ref "R89") (pin "2") (pinfunction "2_2") (pintype "passive"))
      (node (ref "R92") (pin "2") (pinfunction "2_2") (pintype "passive"))
    )
    (net (code "91") (name "Net-(Q6-C)") (class "Default")
      (node (ref "D5") (pin "C") (pinfunction "C_C") (pintype "passive"))
      (node (ref "Q6") (pin "3") (pinfunction "C_3") (pintype "passive"))
    )
    (net (code "92") (name "Net-(Q7-B)") (class "Default")
      (node (ref "Q7") (pin "1") (pinfunction "B_1") (pintype "passive"))
      (node (ref "R88") (pin "2") (pinfunction "2_2") (pintype "passive"))
      (node (ref "R93") (pin "2") (pinfunction "2_2") (pintype "passive"))
    )
    (net (code "93") (name "Net-(Q7-C)") (class "Default")
      (node (ref "D6") (pin "C") (pinfunction "C_C") (pintype "passive"))
      (node (ref "Q7") (pin "3") (pinfunction "C_3") (pintype "passive"))
    )
    (net (code "94") (name "Net-(Q11-B)") (class "Default")
      (node (ref "C83") (pin "1") (pinfunction "1_1") (pintype "passive"))
      (node (ref "Q11") (pin "1") (pinfunction "B_1") (pintype "passive"))
      (node (ref "R163") (pin "1") (pinfunction "1_1") (pintype "passive"))
      (node (ref "R164") (pin "2") (pinfunction "2_2") (pintype "passive"))
    )
    (net (code "95") (name "Net-(U7G-VBAT)") (class "Default")
      (node (ref "C24") (pin "2") (pinfunction "2_2") (pintype "passive"))
      (node (ref "R84") (pin "1") (pinfunction "1_1") (pintype "passive"))
      (node (ref "U7") (pin "6") (pinfunction "VBAT_6") (pintype "power_in"))
    )
    (net (code "96") (name "Net-(U7G-VDDA)") (class "Default")
      (node (ref "C31") (pin "2") (pinfunction "2_2") (pintype "passive"))
      (node (ref "C32") (pin "2") (pinfunction "2_2") (pintype "passive"))
      (node (ref "FB1") (pin "1") (pinfunction "1_1") (pintype "passive"))
      (node (ref "U7") (pin "37") (pinfunction "VDDA_37") (pintype "power_in"))
    )
    (net (code "97") (name "Net-(U7G-VREF+)") (class "Default")
      (node (ref "C33") (pin "2") (pinfunction "2_2") (pintype "passive"))
      (node (ref "C34") (pin "2") (pinfunction "2_2") (pintype "passive"))
      (node (ref "FB2") (pin "1") (pinfunction "1_1") (pintype "passive"))
      (node (ref "U7") (pin "36") (pinfunction "VREF+_36") (pintype "power_in"))
    )
    (net (code "98") (name "unconnected-(U7A-PA4-Pad26)") (class "Default")
      (node (ref "U7") (pin "26") (pinfunction "PA4_26") (pintype "bidirectional"))
    )
    (net (code "99") (name "unconnected-(U7A-PA6-Pad28)") (class "Default")
      (node (ref "U7") (pin "28") (pinfunction "PA6_28") (pintype "bidirectional"))
    )
    (net (code "100") (name "unconnected-(U7A-PA7-Pad29)") (class "Default")
      (node (ref "U7") (pin "29") (pinfunction "PA7_29") (pintype "bidirectional"))
    )
    (net (code "101") (name "unconnected-(U7A-PA8-Pad69)") (class "Default")
      (node (ref "U7") (pin "69") (pinfunction "PA8_69") (pintype "bidirectional"))
    )
    (net (code "102") (name "unconnected-(U7A-PA10-Pad71)") (class "Default")
      (node (ref "U7") (pin "71") (pinfunction "PA10_71") (pintype "bidirectional"))
    )
    (net (code "103") (name "unconnected-(U7B-PB0-Pad32)") (class "Default")
      (node (ref "U7") (pin "32") (pinfunction "PB0_32") (pintype "bidirectional"))
    )
    (net (code "104") (name "unconnected-(U7B-PB1-Pad33)") (class "Default")
      (node (ref "U7") (pin "33") (pinfunction "PB1_33") (pintype "bidirectional"))
    )
    (net (code "105") (name "unconnected-(U7B-PB2-Pad34)") (class "Default")
      (node (ref "U7") (pin "34") (pinfunction "PB2_34") (pintype "bidirectional"))
    )
    (net (code "106") (name "unconnected-(U7B-PB4-Pad91)") (class "Default")
      (node (ref "U7") (pin "91") (pinfunction "PB4_91") (pintype "bidirectional"))
    )
    (net (code "107") (name "unconnected-(U7B-PB5-Pad92)") (class "Default")
      (node (ref "U7") (pin "92") (pinfunction "PB5_92") (pintype "bidirectional"))
    )
    (net (code "108") (name "unconnected-(U7B-PB6-Pad93)") (class "Default")
      (node (ref "U7") (pin "93") (pinfunction "PB6_93") (pintype "bidirectional"))
    )
    (net (code "109") (name "unconnected-(U7C-PC5-Pad31)") (class "Default")
      (node (ref "U7") (pin "31") (pinfunction "PC5_31") (pintype "bidirectional"))
    )
    (net (code "110") (name "unconnected-(U7C-PC13-Pad7)") (class "Default")
      (node (ref "U7") (pin "7") (pinfunction "PC13_7") (pintype "bidirectional"))
    )
    (net (code "111") (name "unconnected-(U7D-PD1-Pad83)") (class "Default")
      (node (ref "U7") (pin "83") (pinfunction "PD1_83") (pintype "bidirectional"))
    )
    (net (code "112") (name "unconnected-(U7D-PD2-Pad84)") (class "Default")
      (node (ref "U7") (pin "84") (pinfunction "PD2_84") (pintype "bidirectional"))
    )
    (net (code "113") (name "unconnected-(U7D-PD3-Pad85)") (class "Default")
      (node (ref "U7") (pin "85") (pinfunction "PD3_85") (pintype "bidirectional"))
    )
    (net (code "114") (name "unconnected-(U7D-PD5-Pad87)") (class "Default")
      (node (ref "U7") (pin "87") (pinfunction "PD5_87") (pintype "bidirectional"))
    )
    (net (code "115") (name "unconnected-(U7D-PD6-Pad88)") (class "Default")
      (node (ref "U7") (pin "88") (pinfunction "PD6_88") (pintype "bidirectional"))
    )
    (net (code "116") (name "unconnected-(U7D-PD7-Pad89)") (class "Default")
      (node (ref "U7") (pin "89") (pinfunction "PD7_89") (pintype "bidirectional"))
    )
    (net (code "117") (name "unconnected-(U7E-PE5-Pad4)") (class "Default")
      (node (ref "U7") (pin "4") (pinfunction "PE5_4") (pintype "bidirectional"))
    )
    (net (code "118") (name "unconnected-(U7F-PF2-Pad19)") (class "Default")
      (node (ref "U7") (pin "19") (pinfunction "PF2_19") (pintype "bidirectional"))
    )
    (net (code "119") (name "unconnected-(U7F-PF9-Pad10)") (class "Default")
      (node (ref "U7") (pin "10") (pinfunction "PF9_10") (pintype "bidirectional"))
    )
    (net (code "120") (name "unconnected-(U7F-PF10-Pad11)") (class "Default")
      (node (ref "U7") (pin "11") (pinfunction "PF10_11") (pintype "bidirectional"))
    )
  )
)
